# capelet_kinetic.net
KiCad netlist of a schematic drawn in EAGLE
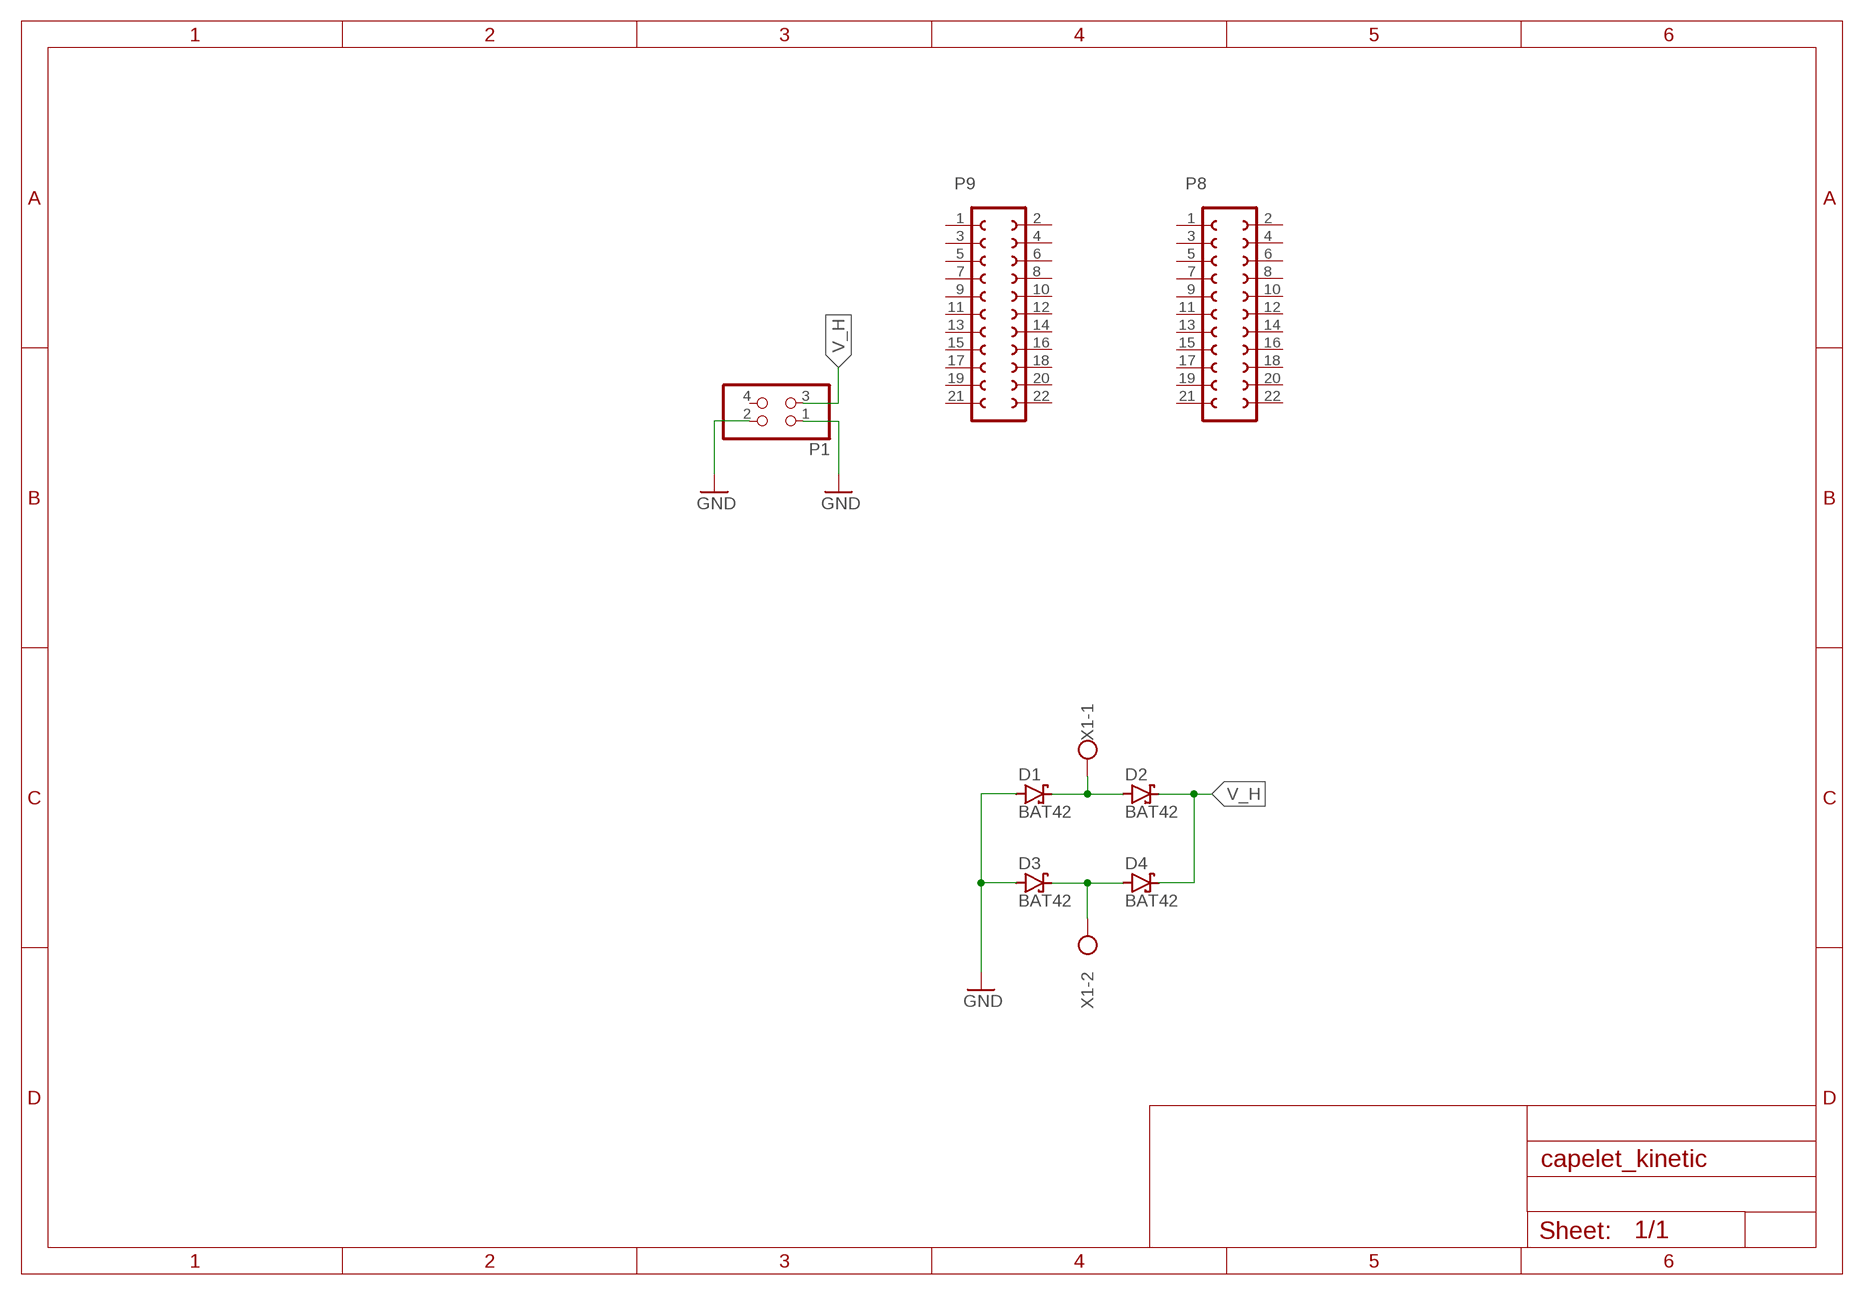
[diagram p0: schematic, sheet 1]

(export (version "E")
  (design (tool "Eeschema 10.0.6"))
  (components
    (comp (ref "D1")
      (value "BAT42")
      (footprint "eagle-import:DO35-10")
      (libsource (lib "eagle-import") (part "BAT42"))
    )
    (comp (ref "D2")
      (value "BAT42")
      (footprint "eagle-import:DO35-10")
      (libsource (lib "eagle-import") (part "BAT42"))
    )
    (comp (ref "D3")
      (value "BAT42")
      (footprint "eagle-import:DO35-10")
      (libsource (lib "eagle-import") (part "BAT42"))
    )
    (comp (ref "D4")
      (value "BAT42")
      (footprint "eagle-import:DO35-10")
      (libsource (lib "eagle-import") (part "BAT42"))
    )
    (comp (ref "P1")
      (value "PINHD-2X2")
      (footprint "eagle-import:2X02")
      (libsource (lib "eagle-import") (part "PINHD-2X2"))
    )
    (comp (ref "P8")
      (value "FE11-2")
      (footprint "eagle-import:FE11-2")
      (libsource (lib "eagle-import") (part "FE11-2"))
    )
    (comp (ref "P9")
      (value "FE11-2")
      (footprint "eagle-import:FE11-2")
      (libsource (lib "eagle-import") (part "FE11-2"))
    )
    (comp (ref "X1")
      (value "W237-102")
      (footprint "eagle-import:W237-102")
      (fields (field (name "MPN") "237-102"))
      (libsource (lib "eagle-import") (part "W237-102"))
    )
  )
  (nets
    (net (code "1") (name "GND") (class "Default")
      (node (ref "D1") (pin "A") (pinfunction "A_A") (pintype "passive"))
      (node (ref "D3") (pin "A") (pinfunction "A_A") (pintype "passive"))
      (node (ref "P1") (pin "1") (pinfunction "1_1") (pintype "passive"))
      (node (ref "P1") (pin "2") (pinfunction "2_2") (pintype "passive"))
    )
    (net (code "2") (name "Net-(X1A-KL)") (class "Default")
      (node (ref "D1") (pin "C") (pinfunction "C_C") (pintype "passive"))
      (node (ref "D2") (pin "A") (pinfunction "A_A") (pintype "passive"))
      (node (ref "X1") (pin "1") (pinfunction "KL_1") (pintype "passive"))
    )
    (net (code "3") (name "Net-(X1B-KL)") (class "Default")
      (node (ref "D3") (pin "C") (pinfunction "C_C") (pintype "passive"))
      (node (ref "D4") (pin "A") (pinfunction "A_A") (pintype "passive"))
      (node (ref "X1") (pin "2") (pinfunction "KL_2") (pintype "passive"))
    )
    (net (code "4") (name "V_H") (class "Default")
      (node (ref "D2") (pin "C") (pinfunction "C_C") (pintype "passive"))
      (node (ref "D4") (pin "C") (pinfunction "C_C") (pintype "passive"))
      (node (ref "P1") (pin "3") (pinfunction "3_3") (pintype "passive"))
    )
    (net (code "5") (name "unconnected-(P1-Pad4)") (class "Default")
      (node (ref "P1") (pin "4") (pinfunction "4_4") (pintype "passive"))
    )
    (net (code "6") (name "unconnected-(P8-25-Pad1)") (class "Default")
      (node (ref "P8") (pin "1") (pinfunction "25_1") (pintype "passive"))
    )
    (net (code "7") (name "unconnected-(P8-26-Pad2)") (class "Default")
      (node (ref "P8") (pin "2") (pinfunction "26_2") (pintype "passive"))
    )
    (net (code "8") (name "unconnected-(P8-27-Pad3)") (class "Default")
      (node (ref "P8") (pin "3") (pinfunction "27_3") (pintype "passive"))
    )
    (net (code "9") (name "unconnected-(P8-28-Pad4)") (class "Default")
      (node (ref "P8") (pin "4") (pinfunction "28_4") (pintype "passive"))
    )
    (net (code "10") (name "unconnected-(P8-29-Pad5)") (class "Default")
      (node (ref "P8") (pin "5") (pinfunction "29_5") (pintype "passive"))
    )
    (net (code "11") (name "unconnected-(P8-30-Pad6)") (class "Default")
      (node (ref "P8") (pin "6") (pinfunction "30_6") (pintype "passive"))
    )
    (net (code "12") (name "unconnected-(P8-31-Pad7)") (class "Default")
      (node (ref "P8") (pin "7") (pinfunction "31_7") (pintype "passive"))
    )
    (net (code "13") (name "unconnected-(P8-32-Pad8)") (class "Default")
      (node (ref "P8") (pin "8") (pinfunction "32_8") (pintype "passive"))
    )
    (net (code "14") (name "unconnected-(P8-33-Pad9)") (class "Default")
      (node (ref "P8") (pin "9") (pinfunction "33_9") (pintype "passive"))
    )
    (net (code "15") (name "unconnected-(P8-34-Pad10)") (class "Default")
      (node (ref "P8") (pin "10") (pinfunction "34_10") (pintype "passive"))
    )
    (net (code "16") (name "unconnected-(P8-35-Pad11)") (class "Default")
      (node (ref "P8") (pin "11") (pinfunction "35_11") (pintype "passive"))
    )
    (net (code "17") (name "unconnected-(P8-36-Pad12)") (class "Default")
      (node (ref "P8") (pin "12") (pinfunction "36_12") (pintype "passive"))
    )
    (net (code "18") (name "unconnected-(P8-37-Pad13)") (class "Default")
      (node (ref "P8") (pin "13") (pinfunction "37_13") (pintype "passive"))
    )
    (net (code "19") (name "unconnected-(P8-38-Pad14)") (class "Default")
      (node (ref "P8") (pin "14") (pinfunction "38_14") (pintype "passive"))
    )
    (net (code "20") (name "unconnected-(P8-39-Pad15)") (class "Default")
      (node (ref "P8") (pin "15") (pinfunction "39_15") (pintype "passive"))
    )
    (net (code "21") (name "unconnected-(P8-40-Pad16)") (class "Default")
      (node (ref "P8") (pin "16") (pinfunction "40_16") (pintype "passive"))
    )
    (net (code "22") (name "unconnected-(P8-41-Pad17)") (class "Default")
      (node (ref "P8") (pin "17") (pinfunction "41_17") (pintype "passive"))
    )
    (net (code "23") (name "unconnected-(P8-42-Pad18)") (class "Default")
      (node (ref "P8") (pin "18") (pinfunction "42_18") (pintype "passive"))
    )
    (net (code "24") (name "unconnected-(P8-43-Pad19)") (class "Default")
      (node (ref "P8") (pin "19") (pinfunction "43_19") (pintype "passive"))
    )
    (net (code "25") (name "unconnected-(P8-44-Pad20)") (class "Default")
      (node (ref "P8") (pin "20") (pinfunction "44_20") (pintype "passive"))
    )
    (net (code "26") (name "unconnected-(P8-45-Pad21)") (class "Default")
      (node (ref "P8") (pin "21") (pinfunction "45_21") (pintype "passive"))
    )
    (net (code "27") (name "unconnected-(P8-46-Pad22)") (class "Default")
      (node (ref "P8") (pin "22") (pinfunction "46_22") (pintype "passive"))
    )
    (net (code "28") (name "unconnected-(P9-25-Pad1)") (class "Default")
      (node (ref "P9") (pin "1") (pinfunction "25_1") (pintype "passive"))
    )
    (net (code "29") (name "unconnected-(P9-26-Pad2)") (class "Default")
      (node (ref "P9") (pin "2") (pinfunction "26_2") (pintype "passive"))
    )
    (net (code "30") (name "unconnected-(P9-27-Pad3)") (class "Default")
      (node (ref "P9") (pin "3") (pinfunction "27_3") (pintype "passive"))
    )
    (net (code "31") (name "unconnected-(P9-28-Pad4)") (class "Default")
      (node (ref "P9") (pin "4") (pinfunction "28_4") (pintype "passive"))
    )
    (net (code "32") (name "unconnected-(P9-29-Pad5)") (class "Default")
      (node (ref "P9") (pin "5") (pinfunction "29_5") (pintype "passive"))
    )
    (net (code "33") (name "unconnected-(P9-30-Pad6)") (class "Default")
      (node (ref "P9") (pin "6") (pinfunction "30_6") (pintype "passive"))
    )
    (net (code "34") (name "unconnected-(P9-31-Pad7)") (class "Default")
      (node (ref "P9") (pin "7") (pinfunction "31_7") (pintype "passive"))
    )
    (net (code "35") (name "unconnected-(P9-32-Pad8)") (class "Default")
      (node (ref "P9") (pin "8") (pinfunction "32_8") (pintype "passive"))
    )
    (net (code "36") (name "unconnected-(P9-33-Pad9)") (class "Default")
      (node (ref "P9") (pin "9") (pinfunction "33_9") (pintype "passive"))
    )
    (net (code "37") (name "unconnected-(P9-34-Pad10)") (class "Default")
      (node (ref "P9") (pin "10") (pinfunction "34_10") (pintype "passive"))
    )
    (net (code "38") (name "unconnected-(P9-35-Pad11)") (class "Default")
      (node (ref "P9") (pin "11") (pinfunction "35_11") (pintype "passive"))
    )
    (net (code "39") (name "unconnected-(P9-36-Pad12)") (class "Default")
      (node (ref "P9") (pin "12") (pinfunction "36_12") (pintype "passive"))
    )
    (net (code "40") (name "unconnected-(P9-37-Pad13)") (class "Default")
      (node (ref "P9") (pin "13") (pinfunction "37_13") (pintype "passive"))
    )
    (net (code "41") (name "unconnected-(P9-38-Pad14)") (class "Default")
      (node (ref "P9") (pin "14") (pinfunction "38_14") (pintype "passive"))
    )
    (net (code "42") (name "unconnected-(P9-39-Pad15)") (class "Default")
      (node (ref "P9") (pin "15") (pinfunction "39_15") (pintype "passive"))
    )
    (net (code "43") (name "unconnected-(P9-40-Pad16)") (class "Default")
      (node (ref "P9") (pin "16") (pinfunction "40_16") (pintype "passive"))
    )
    (net (code "44") (name "unconnected-(P9-41-Pad17)") (class "Default")
      (node (ref "P9") (pin "17") (pinfunction "41_17") (pintype "passive"))
    )
    (net (code "45") (name "unconnected-(P9-42-Pad18)") (class "Default")
      (node (ref "P9") (pin "18") (pinfunction "42_18") (pintype "passive"))
    )
    (net (code "46") (name "unconnected-(P9-43-Pad19)") (class "Default")
      (node (ref "P9") (pin "19") (pinfunction "43_19") (pintype "passive"))
    )
    (net (code "47") (name "unconnected-(P9-44-Pad20)") (class "Default")
      (node (ref "P9") (pin "20") (pinfunction "44_20") (pintype "passive"))
    )
    (net (code "48") (name "unconnected-(P9-45-Pad21)") (class "Default")
      (node (ref "P9") (pin "21") (pinfunction "45_21") (pintype "passive"))
    )
    (net (code "49") (name "unconnected-(P9-46-Pad22)") (class "Default")
      (node (ref "P9") (pin "22") (pinfunction "46_22") (pintype "passive"))
    )
  )
)
